# REL_IF.net
KiCad netlist of a schematic drawn in Altium Designer
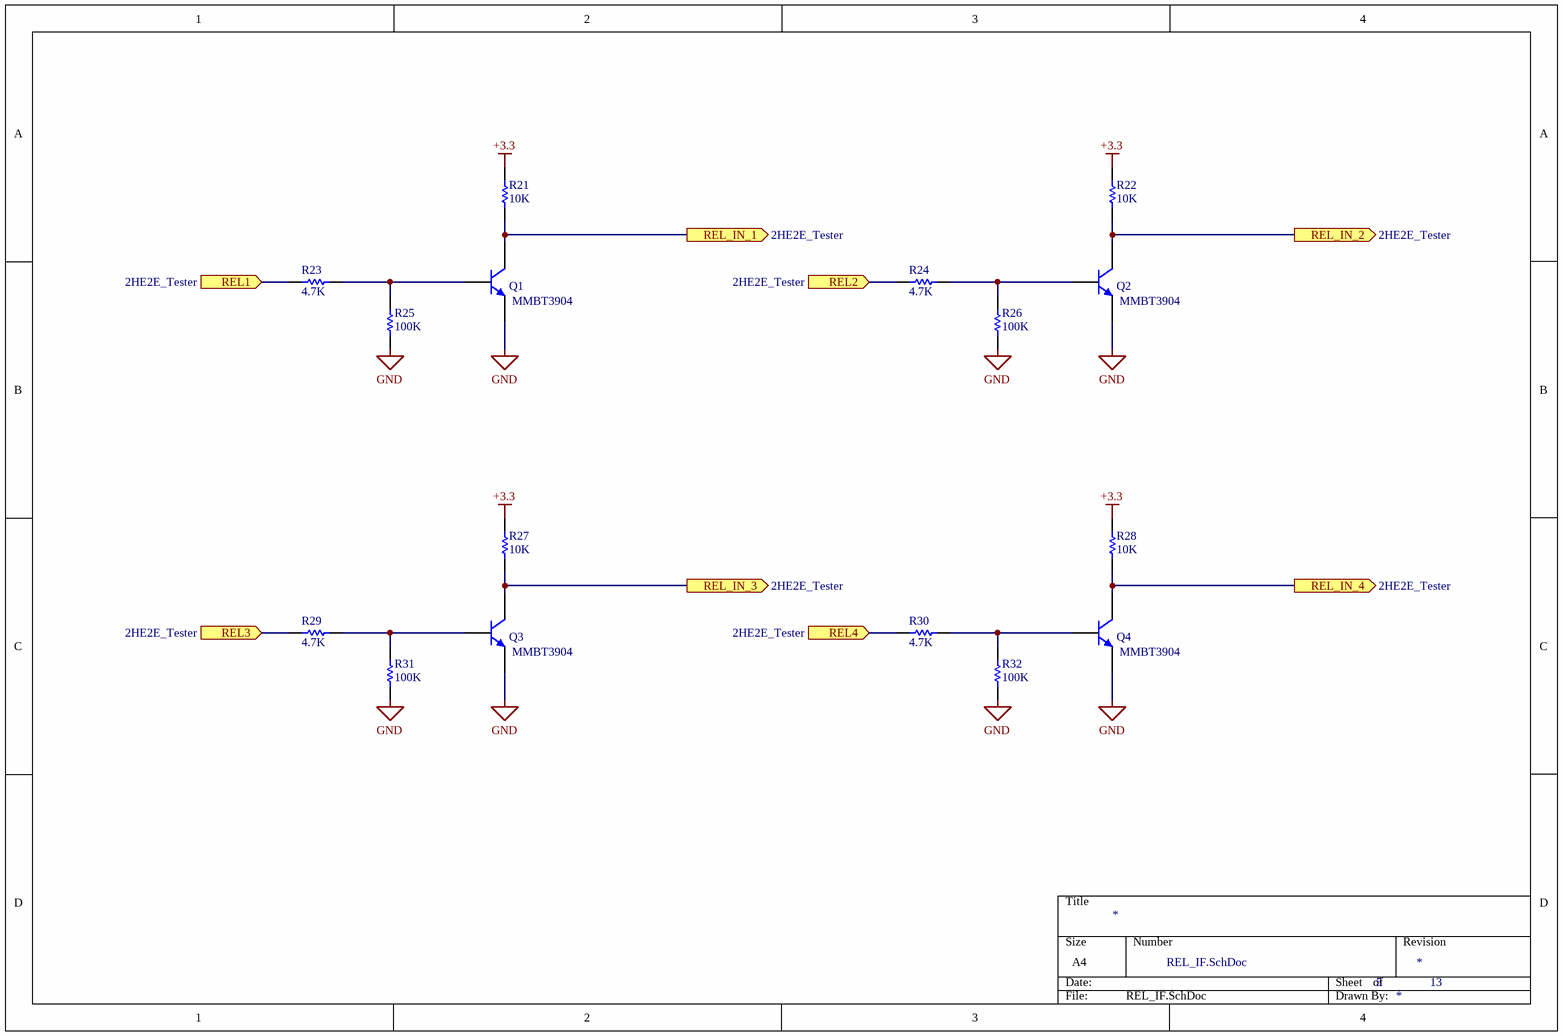
[diagram p0: REL_IF.SchDoc]

(export (version "E")
  (design (tool "Eeschema 10.0.6"))
  (components
    (comp (ref "Q1")
      (value "MMBT3904")
      (footprint "SOT23 BSR14")
      (description "NPN Bipolar Transistor")
      (libsource (lib "Plume") (part "Transistor NPN"))
    )
    (comp (ref "Q2")
      (value "MMBT3904")
      (footprint "SOT23 BSR14")
      (description "NPN Bipolar Transistor")
      (libsource (lib "Plume") (part "Transistor NPN"))
    )
    (comp (ref "Q3")
      (value "MMBT3904")
      (footprint "SOT23 BSR14")
      (description "NPN Bipolar Transistor")
      (libsource (lib "Plume") (part "Transistor NPN"))
    )
    (comp (ref "Q4")
      (value "MMBT3904")
      (footprint "SOT23 BSR14")
      (description "NPN Bipolar Transistor")
      (libsource (lib "Plume") (part "Transistor NPN"))
    )
    (comp (ref "R21")
      (value "10K")
      (footprint "0603M")
      (description "Resistor")
      (libsource (lib "Plume") (part "Resistor"))
    )
    (comp (ref "R22")
      (value "10K")
      (footprint "0603M")
      (description "Resistor")
      (libsource (lib "Plume") (part "Resistor"))
    )
    (comp (ref "R23")
      (value "4.7K")
      (footprint "0603M")
      (description "Resistor")
      (libsource (lib "Plume") (part "Resistor"))
    )
    (comp (ref "R24")
      (value "4.7K")
      (footprint "0603M")
      (description "Resistor")
      (libsource (lib "Plume") (part "Resistor"))
    )
    (comp (ref "R25")
      (value "100K")
      (footprint "0603M")
      (description "Resistor")
      (libsource (lib "Plume") (part "Resistor"))
    )
    (comp (ref "R26")
      (value "100K")
      (footprint "0603M")
      (description "Resistor")
      (libsource (lib "Plume") (part "Resistor"))
    )
    (comp (ref "R27")
      (value "10K")
      (footprint "0603M")
      (description "Resistor")
      (libsource (lib "Plume") (part "Resistor"))
    )
    (comp (ref "R28")
      (value "10K")
      (footprint "0603M")
      (description "Resistor")
      (libsource (lib "Plume") (part "Resistor"))
    )
    (comp (ref "R29")
      (value "4.7K")
      (footprint "0603M")
      (description "Resistor")
      (libsource (lib "Plume") (part "Resistor"))
    )
    (comp (ref "R30")
      (value "4.7K")
      (footprint "0603M")
      (description "Resistor")
      (libsource (lib "Plume") (part "Resistor"))
    )
    (comp (ref "R31")
      (value "100K")
      (footprint "0603M")
      (description "Resistor")
      (libsource (lib "Plume") (part "Resistor"))
    )
    (comp (ref "R32")
      (value "100K")
      (footprint "0603M")
      (description "Resistor")
      (libsource (lib "Plume") (part "Resistor"))
    )
  )
  (nets
    (net (code "1") (name "+3.3") (class "Default")
      (node (ref "R21") (pin "1") (pinfunction "1_1") (pintype "passive"))
      (node (ref "R22") (pin "1") (pinfunction "1_1") (pintype "passive"))
      (node (ref "R27") (pin "1") (pinfunction "1_1") (pintype "passive"))
      (node (ref "R28") (pin "1") (pinfunction "1_1") (pintype "passive"))
    )
    (net (code "2") (name "/REL1") (class "Default")
      (node (ref "R23") (pin "1") (pinfunction "1_1") (pintype "passive"))
    )
    (net (code "3") (name "/REL2") (class "Default")
      (node (ref "R24") (pin "1") (pinfunction "1_1") (pintype "passive"))
    )
    (net (code "4") (name "/REL3") (class "Default")
      (node (ref "R29") (pin "1") (pinfunction "1_1") (pintype "passive"))
    )
    (net (code "5") (name "/REL4") (class "Default")
      (node (ref "R30") (pin "1") (pinfunction "1_1") (pintype "passive"))
    )
    (net (code "6") (name "/REL_IN_1") (class "Default")
      (node (ref "Q1") (pin "1") (pinfunction "C_1") (pintype "passive"))
      (node (ref "R21") (pin "2") (pinfunction "2_2") (pintype "passive"))
    )
    (net (code "7") (name "/REL_IN_2") (class "Default")
      (node (ref "Q2") (pin "1") (pinfunction "C_1") (pintype "passive"))
      (node (ref "R22") (pin "2") (pinfunction "2_2") (pintype "passive"))
    )
    (net (code "8") (name "/REL_IN_3") (class "Default")
      (node (ref "Q3") (pin "1") (pinfunction "C_1") (pintype "passive"))
      (node (ref "R27") (pin "2") (pinfunction "2_2") (pintype "passive"))
    )
    (net (code "9") (name "/REL_IN_4") (class "Default")
      (node (ref "Q4") (pin "1") (pinfunction "C_1") (pintype "passive"))
      (node (ref "R28") (pin "2") (pinfunction "2_2") (pintype "passive"))
    )
    (net (code "10") (name "GND") (class "Default")
      (node (ref "Q1") (pin "3") (pinfunction "E_3") (pintype "passive"))
      (node (ref "Q2") (pin "3") (pinfunction "E_3") (pintype "passive"))
      (node (ref "Q3") (pin "3") (pinfunction "E_3") (pintype "passive"))
      (node (ref "Q4") (pin "3") (pinfunction "E_3") (pintype "passive"))
      (node (ref "R25") (pin "2") (pinfunction "2_2") (pintype "passive"))
      (node (ref "R26") (pin "2") (pinfunction "2_2") (pintype "passive"))
      (node (ref "R31") (pin "2") (pinfunction "2_2") (pintype "passive"))
      (node (ref "R32") (pin "2") (pinfunction "2_2") (pintype "passive"))
    )
    (net (code "11") (name "Net-(Q1-B)") (class "Default")
      (node (ref "Q1") (pin "2") (pinfunction "B_2") (pintype "passive"))
      (node (ref "R23") (pin "2") (pinfunction "2_2") (pintype "passive"))
      (node (ref "R25") (pin "1") (pinfunction "1_1") (pintype "passive"))
    )
    (net (code "12") (name "Net-(Q2-B)") (class "Default")
      (node (ref "Q2") (pin "2") (pinfunction "B_2") (pintype "passive"))
      (node (ref "R24") (pin "2") (pinfunction "2_2") (pintype "passive"))
      (node (ref "R26") (pin "1") (pinfunction "1_1") (pintype "passive"))
    )
    (net (code "13") (name "Net-(Q3-B)") (class "Default")
      (node (ref "Q3") (pin "2") (pinfunction "B_2") (pintype "passive"))
      (node (ref "R29") (pin "2") (pinfunction "2_2") (pintype "passive"))
      (node (ref "R31") (pin "1") (pinfunction "1_1") (pintype "passive"))
    )
    (net (code "14") (name "Net-(Q4-B)") (class "Default")
      (node (ref "Q4") (pin "2") (pinfunction "B_2") (pintype "passive"))
      (node (ref "R30") (pin "2") (pinfunction "2_2") (pintype "passive"))
      (node (ref "R32") (pin "1") (pinfunction "1_1") (pintype "passive"))
    )
  )
)
